# ChargingSystem.net
KiCad netlist of a schematic drawn in Altium Designer
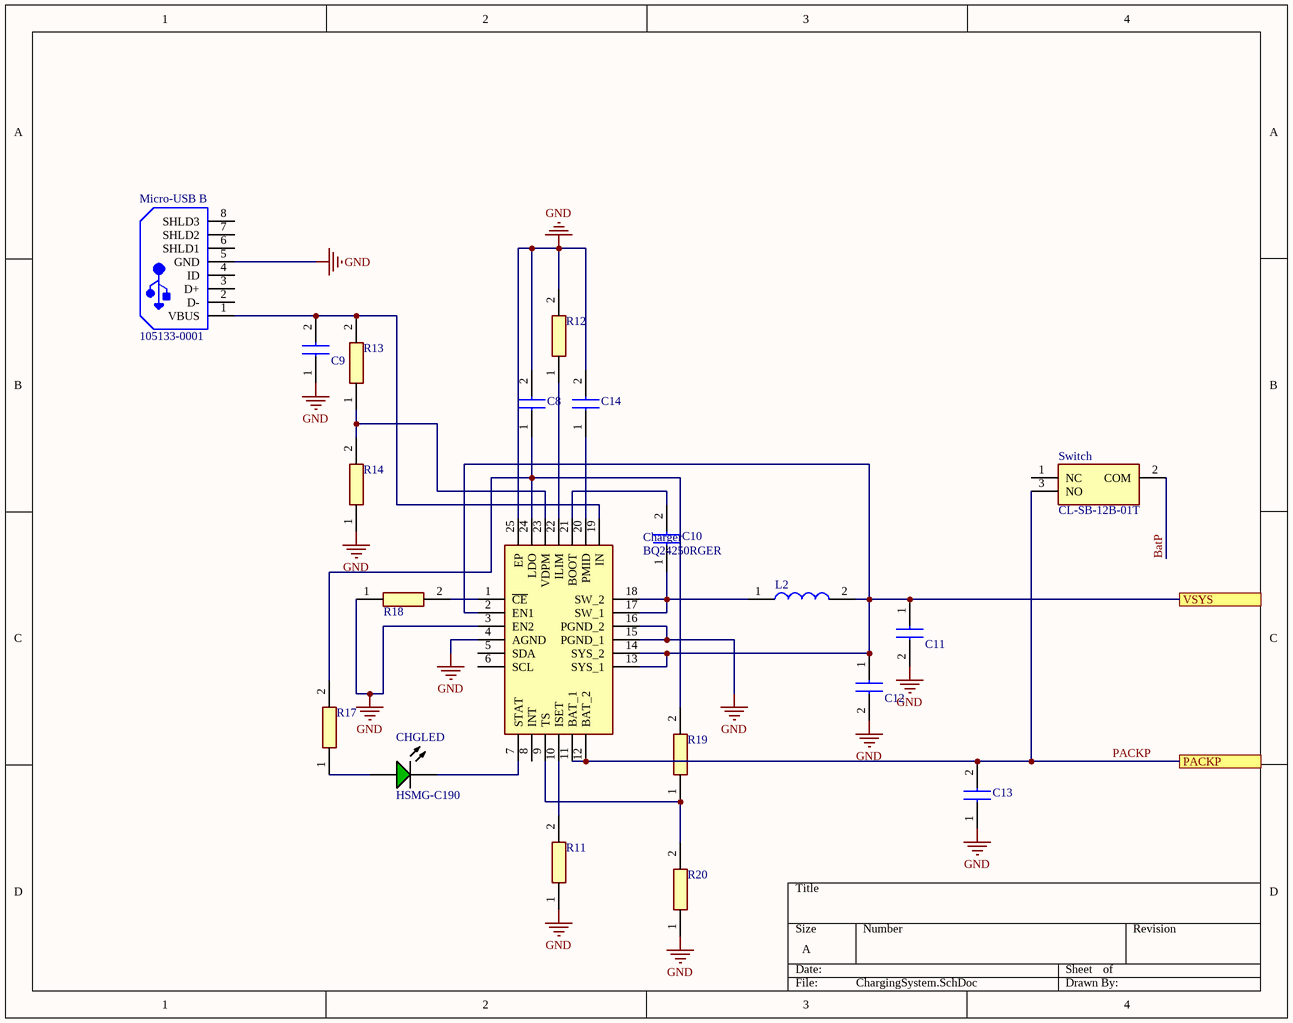
[diagram p0: ChargingSystem.SchDoc]

(export (version "E")
  (design (tool "Eeschema 10.0.6"))
  (components
    (comp (ref "C8")
      (value "C0603C150K5GAC")
      (footprint "SamacSys:CAPC1608X87N")
      (description "Capacitor")
      (fields (field (name "MOUSER PART NUMBER") "80-C0603C150K5GAC"))
      (libsource (lib "*") (part "C0603C150K5GAC"))
    )
    (comp (ref "C9")
      (value "C0603C150K5GAC")
      (footprint "SamacSys:CAPC1608X87N")
      (description "Capacitor")
      (fields (field (name "MOUSER PART NUMBER") "80-C0603C150K5GAC"))
      (libsource (lib "*") (part "C0603C150K5GAC"))
    )
    (comp (ref "C10")
      (value "C0603C150K5GAC")
      (footprint "SamacSys:CAPC1608X87N")
      (description "Capacitor")
      (fields (field (name "MOUSER PART NUMBER") "80-C0603C150K5GAC"))
      (libsource (lib "*") (part "C0603C150K5GAC"))
    )
    (comp (ref "C11")
      (value "C0603C150K5GAC")
      (footprint "SamacSys:CAPC1608X87N")
      (description "Capacitor")
      (fields (field (name "MOUSER PART NUMBER") "80-C0603C150K5GAC"))
      (libsource (lib "*") (part "C0603C150K5GAC"))
    )
    (comp (ref "C12")
      (value "C0603C150K5GAC")
      (footprint "SamacSys:CAPC1608X87N")
      (description "Capacitor")
      (fields (field (name "MOUSER PART NUMBER") "80-C0603C150K5GAC"))
      (libsource (lib "*") (part "C0603C150K5GAC"))
    )
    (comp (ref "C13")
      (value "C0603C150K5GAC")
      (footprint "SamacSys:CAPC1608X87N")
      (description "Capacitor")
      (fields (field (name "MOUSER PART NUMBER") "80-C0603C150K5GAC"))
      (libsource (lib "*") (part "C0603C150K5GAC"))
    )
    (comp (ref "C14")
      (value "C0603C150K5GAC")
      (footprint "SamacSys:CAPC1608X87N")
      (description "Capacitor")
      (fields (field (name "MOUSER PART NUMBER") "80-C0603C150K5GAC"))
      (libsource (lib "*") (part "C0603C150K5GAC"))
    )
    (comp (ref "Charger")
      (value "BQ24250RGER")
      (footprint "SamacSys:QFN50P400X400X100-25N-D")
      (description "Integrated Circuit")
      (fields (field (name "MOUSER PART NUMBER") "595-BQ24250RGER"))
      (libsource (lib "SamacSys") (part "BQ24250RGER"))
    )
    (comp (ref "CHGLED")
      (value "HSMG-C190")
      (footprint "AVAG-HSMX-C190_V")
      (description "Chip LED, Green, 2.2 V, -40 to 85 degC, 2-Pin SMD, RoHS, Tape and Reel")
      (libsource (lib "Altium Content Vault") (part "LED-GREEN-AK-2"))
    )
    (comp (ref "L2")
      (value "0603CS-47NXGLU")
      (footprint "SamacSys:0603CS82NXGLW")
      (description "Inductor")
      (fields (field (name "MOUSER PART NUMBER") "994-0603CS-47NXGLU"))
      (libsource (lib "*") (part "0603CS-47NXGLU"))
    )
    (comp (ref "Micro-USB B")
      (value "105133-0001")
      (footprint "MOLX-105133-0001_V")
      (description "Micro-USB B Receptacle, Vertical, -30 to 85 degC, 5-Pin SMD, RoHS, Tape and Reel")
      (fields (field (name "MANUFACTURER") "Molex"))
      (libsource (lib "Altium Content Vault") (part "USB-5-3SHLD"))
    )
    (comp (ref "R11")
      (value "CRCW06034K70JNEA")
      (footprint "SamacSys:RESC1608X50N")
      (description "Resistor")
      (fields (field (name "MOUSER PART NUMBER") "71-CRCW0603J-4.7K-E3"))
      (libsource (lib "*") (part "CRCW06034K70JNEA"))
    )
    (comp (ref "R12")
      (value "CRCW06034K70JNEA")
      (footprint "SamacSys:RESC1608X50N")
      (description "Resistor")
      (fields (field (name "MOUSER PART NUMBER") "71-CRCW0603J-4.7K-E3"))
      (libsource (lib "*") (part "CRCW06034K70JNEA"))
    )
    (comp (ref "R13")
      (value "CRCW06034K70JNEA")
      (footprint "SamacSys:RESC1608X50N")
      (description "Resistor")
      (fields (field (name "MOUSER PART NUMBER") "71-CRCW0603J-4.7K-E3"))
      (libsource (lib "*") (part "CRCW06034K70JNEA"))
    )
    (comp (ref "R14")
      (value "CRCW06034K70JNEA")
      (footprint "SamacSys:RESC1608X50N")
      (description "Resistor")
      (fields (field (name "MOUSER PART NUMBER") "71-CRCW0603J-4.7K-E3"))
      (libsource (lib "*") (part "CRCW06034K70JNEA"))
    )
    (comp (ref "R17")
      (value "CRCW06034K70JNEA")
      (footprint "SamacSys:RESC1608X50N")
      (description "Resistor")
      (fields (field (name "MOUSER PART NUMBER") "71-CRCW0603J-4.7K-E3"))
      (libsource (lib "*") (part "CRCW06034K70JNEA"))
    )
    (comp (ref "R18")
      (value "CRCW06034K70JNEA")
      (footprint "SamacSys:RESC1608X50N")
      (description "Resistor")
      (fields (field (name "MOUSER PART NUMBER") "71-CRCW0603J-4.7K-E3"))
      (libsource (lib "") (part "CRCW06034K70JNEA_1"))
    )
    (comp (ref "R19")
      (value "CRCW06034K70JNEA")
      (footprint "SamacSys:RESC1608X50N")
      (description "Resistor")
      (fields (field (name "MOUSER PART NUMBER") "71-CRCW0603J-4.7K-E3"))
      (libsource (lib "*") (part "CRCW06034K70JNEA"))
    )
    (comp (ref "R20")
      (value "CRCW06034K70JNEA")
      (footprint "SamacSys:RESC1608X50N")
      (description "Resistor")
      (fields (field (name "MOUSER PART NUMBER") "71-CRCW0603J-4.7K-E3"))
      (libsource (lib "*") (part "CRCW06034K70JNEA"))
    )
    (comp (ref "Switch")
      (value "CL-SB-12B-01T")
      (footprint "SamacSys:CLSB12B01T")
      (description "Switch")
      (libsource (lib "*") (part "CL-SB-12B-01T"))
    )
  )
  (nets
    (net (code "1") (name "/BatP") (class "Default")
      (node (ref "Switch") (pin "2") (pinfunction "COM_2") (pintype "passive"))
    )
    (net (code "2") (name "/PACKP") (class "Default")
      (node (ref "C13") (pin "2") (pinfunction "2_2") (pintype "passive"))
      (node (ref "Charger") (pin "11") (pinfunction "BAT_1_11") (pintype "passive"))
      (node (ref "Charger") (pin "12") (pinfunction "BAT_2_12") (pintype "passive"))
      (node (ref "Switch") (pin "3") (pinfunction "NO_3") (pintype "passive"))
    )
    (net (code "3") (name "/VSYS") (class "Default")
      (node (ref "C11") (pin "1") (pinfunction "1_1") (pintype "passive"))
      (node (ref "C12") (pin "1") (pinfunction "1_1") (pintype "passive"))
      (node (ref "Charger") (pin "13") (pinfunction "SYS_1_13") (pintype "passive"))
      (node (ref "Charger") (pin "14") (pinfunction "SYS_2_14") (pintype "passive"))
      (node (ref "Charger") (pin "2") (pinfunction "EN1_2") (pintype "passive"))
      (node (ref "L2") (pin "2") (pinfunction "2_2") (pintype "passive"))
    )
    (net (code "4") (name "GND") (class "Default")
      (node (ref "C11") (pin "2") (pinfunction "2_2") (pintype "passive"))
      (node (ref "C12") (pin "2") (pinfunction "2_2") (pintype "passive"))
      (node (ref "C13") (pin "1") (pinfunction "1_1") (pintype "passive"))
      (node (ref "C14") (pin "2") (pinfunction "2_2") (pintype "passive"))
      (node (ref "C8") (pin "2") (pinfunction "2_2") (pintype "passive"))
      (node (ref "C9") (pin "1") (pinfunction "1_1") (pintype "passive"))
      (node (ref "Charger") (pin "15") (pinfunction "PGND_1_15") (pintype "passive"))
      (node (ref "Charger") (pin "16") (pinfunction "PGND_2_16") (pintype "passive"))
      (node (ref "Charger") (pin "25") (pinfunction "EP_25") (pintype "passive"))
      (node (ref "Charger") (pin "3") (pinfunction "EN2_3") (pintype "passive"))
      (node (ref "Charger") (pin "4") (pinfunction "AGND_4") (pintype "passive"))
      (node (ref "Micro-USB B") (pin "5") (pinfunction "GND_5") (pintype "passive"))
      (node (ref "R11") (pin "1") (pinfunction "1_1") (pintype "passive"))
      (node (ref "R12") (pin "2") (pinfunction "2_2") (pintype "passive"))
      (node (ref "R14") (pin "1") (pinfunction "1_1") (pintype "passive"))
      (node (ref "R18") (pin "1") (pinfunction "1_1") (pintype "passive"))
      (node (ref "R20") (pin "1") (pinfunction "1_1") (pintype "passive"))
    )
    (net (code "5") (name "Net-(CHGLED-A)") (class "Default")
      (node (ref "CHGLED") (pin "1") (pinfunction "A_1") (pintype "passive"))
      (node (ref "R17") (pin "1") (pinfunction "1_1") (pintype "passive"))
    )
    (net (code "6") (name "Net-(CHGLED-K)") (class "Default")
      (node (ref "CHGLED") (pin "2") (pinfunction "K_2") (pintype "passive"))
      (node (ref "Charger") (pin "7") (pinfunction "STAT_7") (pintype "passive"))
    )
    (net (code "7") (name "Net-(Charger-BOOT)") (class "Default")
      (node (ref "C10") (pin "2") (pinfunction "2_2") (pintype "passive"))
      (node (ref "Charger") (pin "21") (pinfunction "BOOT_21") (pintype "passive"))
    )
    (net (code "8") (name "Net-(Charger-ILIM)") (class "Default")
      (node (ref "Charger") (pin "22") (pinfunction "ILIM_22") (pintype "passive"))
      (node (ref "R12") (pin "1") (pinfunction "1_1") (pintype "passive"))
    )
    (net (code "9") (name "Net-(Charger-IN)") (class "Default")
      (node (ref "C9") (pin "2") (pinfunction "2_2") (pintype "passive"))
      (node (ref "Charger") (pin "19") (pinfunction "IN_19") (pintype "passive"))
      (node (ref "Micro-USB B") (pin "1") (pinfunction "VBUS_1") (pintype "passive"))
      (node (ref "R13") (pin "2") (pinfunction "2_2") (pintype "passive"))
    )
    (net (code "10") (name "Net-(Charger-ISET)") (class "Default")
      (node (ref "Charger") (pin "10") (pinfunction "ISET_10") (pintype "passive"))
      (node (ref "R11") (pin "2") (pinfunction "2_2") (pintype "passive"))
    )
    (net (code "11") (name "Net-(Charger-LDO)") (class "Default")
      (node (ref "C8") (pin "1") (pinfunction "1_1") (pintype "passive"))
      (node (ref "Charger") (pin "24") (pinfunction "LDO_24") (pintype "passive"))
      (node (ref "R17") (pin "2") (pinfunction "2_2") (pintype "passive"))
      (node (ref "R19") (pin "2") (pinfunction "2_2") (pintype "passive"))
    )
    (net (code "12") (name "Net-(Charger-PMID)") (class "Default")
      (node (ref "C14") (pin "1") (pinfunction "1_1") (pintype "passive"))
      (node (ref "Charger") (pin "20") (pinfunction "PMID_20") (pintype "passive"))
    )
    (net (code "13") (name "Net-(Charger-SW_1)") (class "Default")
      (node (ref "C10") (pin "1") (pinfunction "1_1") (pintype "passive"))
      (node (ref "Charger") (pin "17") (pinfunction "SW_1_17") (pintype "passive"))
      (node (ref "Charger") (pin "18") (pinfunction "SW_2_18") (pintype "passive"))
      (node (ref "L2") (pin "1") (pinfunction "1_1") (pintype "passive"))
    )
    (net (code "14") (name "Net-(Charger-TS)") (class "Default")
      (node (ref "Charger") (pin "9") (pinfunction "TS_9") (pintype "passive"))
      (node (ref "R19") (pin "1") (pinfunction "1_1") (pintype "passive"))
      (node (ref "R20") (pin "2") (pinfunction "2_2") (pintype "passive"))
    )
    (net (code "15") (name "Net-(Charger-VDPM)") (class "Default")
      (node (ref "Charger") (pin "23") (pinfunction "VDPM_23") (pintype "passive"))
      (node (ref "R13") (pin "1") (pinfunction "1_1") (pintype "passive"))
      (node (ref "R14") (pin "2") (pinfunction "2_2") (pintype "passive"))
    )
    (net (code "16") (name "Net-(Charger-~{CE})") (class "Default")
      (node (ref "Charger") (pin "1") (pinfunction "~{CE}_1") (pintype "passive"))
      (node (ref "R18") (pin "2") (pinfunction "2_2") (pintype "passive"))
    )
    (net (code "17") (name "unconnected-(Charger-INT-Pad8)") (class "Default")
      (node (ref "Charger") (pin "8") (pinfunction "INT_8") (pintype "passive"))
    )
    (net (code "18") (name "unconnected-(Charger-SCL-Pad6)") (class "Default")
      (node (ref "Charger") (pin "6") (pinfunction "SCL_6") (pintype "passive"))
    )
    (net (code "19") (name "unconnected-(Charger-SDA-Pad5)") (class "Default")
      (node (ref "Charger") (pin "5") (pinfunction "SDA_5") (pintype "passive"))
    )
    (net (code "20") (name "unconnected-(Micro-USB B-D+-Pad3)") (class "Default")
      (node (ref "Micro-USB B") (pin "3") (pinfunction "D+_3") (pintype "passive"))
    )
    (net (code "21") (name "unconnected-(Micro-USB B-D--Pad2)") (class "Default")
      (node (ref "Micro-USB B") (pin "2") (pinfunction "D-_2") (pintype "passive"))
    )
    (net (code "22") (name "unconnected-(Micro-USB B-ID-Pad4)") (class "Default")
      (node (ref "Micro-USB B") (pin "4") (pinfunction "ID_4") (pintype "passive"))
    )
    (net (code "23") (name "unconnected-(Micro-USB B-SHLD1-Pad6)") (class "Default")
      (node (ref "Micro-USB B") (pin "6") (pinfunction "SHLD1_6") (pintype "passive"))
    )
    (net (code "24") (name "unconnected-(Micro-USB B-SHLD2-Pad7)") (class "Default")
      (node (ref "Micro-USB B") (pin "7") (pinfunction "SHLD2_7") (pintype "passive"))
    )
    (net (code "25") (name "unconnected-(Micro-USB B-SHLD3-Pad8)") (class "Default")
      (node (ref "Micro-USB B") (pin "8") (pinfunction "SHLD3_8") (pintype "passive"))
    )
    (net (code "26") (name "unconnected-(Switch-NC-Pad1)") (class "Default")
      (node (ref "Switch") (pin "1") (pinfunction "NC_1") (pintype "passive"))
    )
  )
)
